# multiplexRGBtry1.net
KiCad netlist of a schematic drawn in EAGLE
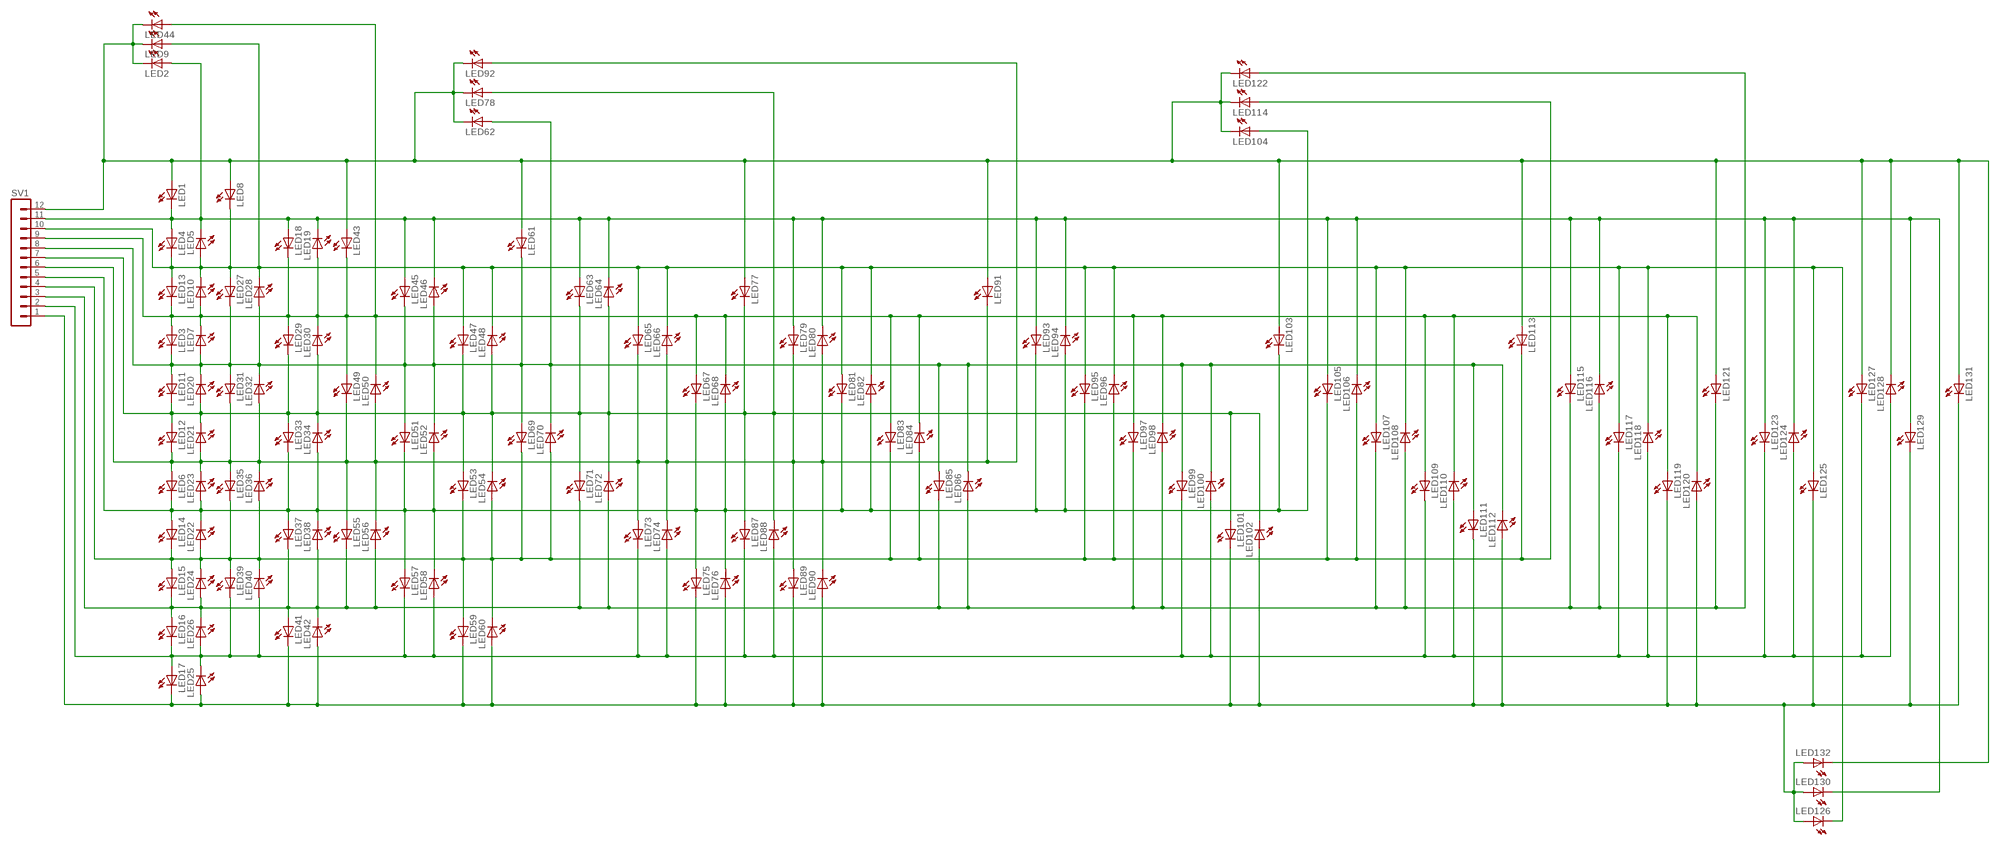
[diagram p0: schematic, sheet 1]

(export (version "E")
  (design (tool "Eeschema 10.0.6"))
  (components
    (comp (ref "LED1")
      (value "LED5MM")
      (footprint "eagle-import:LED5MM")
      (libsource (lib "eagle-import") (part "LED5MM"))
    )
    (comp (ref "LED2")
      (value "LED5MM")
      (footprint "eagle-import:LED5MM")
      (libsource (lib "eagle-import") (part "LED5MM"))
    )
    (comp (ref "LED3")
      (value "LED5MM")
      (footprint "eagle-import:LED5MM")
      (libsource (lib "eagle-import") (part "LED5MM"))
    )
    (comp (ref "LED4")
      (value "LED5MM")
      (footprint "eagle-import:LED5MM")
      (libsource (lib "eagle-import") (part "LED5MM"))
    )
    (comp (ref "LED5")
      (value "LED5MM")
      (footprint "eagle-import:LED5MM")
      (libsource (lib "eagle-import") (part "LED5MM"))
    )
    (comp (ref "LED6")
      (value "LED5MM")
      (footprint "eagle-import:LED5MM")
      (libsource (lib "eagle-import") (part "LED5MM"))
    )
    (comp (ref "LED7")
      (value "LED5MM")
      (footprint "eagle-import:LED5MM")
      (libsource (lib "eagle-import") (part "LED5MM"))
    )
    (comp (ref "LED8")
      (value "LED5MM")
      (footprint "eagle-import:LED5MM")
      (libsource (lib "eagle-import") (part "LED5MM"))
    )
    (comp (ref "LED9")
      (value "LED5MM")
      (footprint "eagle-import:LED5MM")
      (libsource (lib "eagle-import") (part "LED5MM"))
    )
    (comp (ref "LED10")
      (value "LED5MM")
      (footprint "eagle-import:LED5MM")
      (libsource (lib "eagle-import") (part "LED5MM"))
    )
    (comp (ref "LED11")
      (value "LED5MM")
      (footprint "eagle-import:LED5MM")
      (libsource (lib "eagle-import") (part "LED5MM"))
    )
    (comp (ref "LED12")
      (value "LED5MM")
      (footprint "eagle-import:LED5MM")
      (libsource (lib "eagle-import") (part "LED5MM"))
    )
    (comp (ref "LED13")
      (value "LED5MM")
      (footprint "eagle-import:LED5MM")
      (libsource (lib "eagle-import") (part "LED5MM"))
    )
    (comp (ref "LED14")
      (value "LED5MM")
      (footprint "eagle-import:LED5MM")
      (libsource (lib "eagle-import") (part "LED5MM"))
    )
    (comp (ref "LED15")
      (value "LED5MM")
      (footprint "eagle-import:LED5MM")
      (libsource (lib "eagle-import") (part "LED5MM"))
    )
    (comp (ref "LED16")
      (value "LED5MM")
      (footprint "eagle-import:LED5MM")
      (libsource (lib "eagle-import") (part "LED5MM"))
    )
    (comp (ref "LED17")
      (value "LED5MM")
      (footprint "eagle-import:LED5MM")
      (libsource (lib "eagle-import") (part "LED5MM"))
    )
    (comp (ref "LED18")
      (value "LED5MM")
      (footprint "eagle-import:LED5MM")
      (libsource (lib "eagle-import") (part "LED5MM"))
    )
    (comp (ref "LED19")
      (value "LED5MM")
      (footprint "eagle-import:LED5MM")
      (libsource (lib "eagle-import") (part "LED5MM"))
    )
    (comp (ref "LED20")
      (value "LED5MM")
      (footprint "eagle-import:LED5MM")
      (libsource (lib "eagle-import") (part "LED5MM"))
    )
    (comp (ref "LED21")
      (value "LED5MM")
      (footprint "eagle-import:LED5MM")
      (libsource (lib "eagle-import") (part "LED5MM"))
    )
    (comp (ref "LED22")
      (value "LED5MM")
      (footprint "eagle-import:LED5MM")
      (libsource (lib "eagle-import") (part "LED5MM"))
    )
    (comp (ref "LED23")
      (value "LED5MM")
      (footprint "eagle-import:LED5MM")
      (libsource (lib "eagle-import") (part "LED5MM"))
    )
    (comp (ref "LED24")
      (value "LED5MM")
      (footprint "eagle-import:LED5MM")
      (libsource (lib "eagle-import") (part "LED5MM"))
    )
    (comp (ref "LED25")
      (value "LED5MM")
      (footprint "eagle-import:LED5MM")
      (libsource (lib "eagle-import") (part "LED5MM"))
    )
    (comp (ref "LED26")
      (value "LED5MM")
      (footprint "eagle-import:LED5MM")
      (libsource (lib "eagle-import") (part "LED5MM"))
    )
    (comp (ref "LED27")
      (value "LED5MM")
      (footprint "eagle-import:LED5MM")
      (libsource (lib "eagle-import") (part "LED5MM"))
    )
    (comp (ref "LED28")
      (value "LED5MM")
      (footprint "eagle-import:LED5MM")
      (libsource (lib "eagle-import") (part "LED5MM"))
    )
    (comp (ref "LED29")
      (value "LED5MM")
      (footprint "eagle-import:LED5MM")
      (libsource (lib "eagle-import") (part "LED5MM"))
    )
    (comp (ref "LED30")
      (value "LED5MM")
      (footprint "eagle-import:LED5MM")
      (libsource (lib "eagle-import") (part "LED5MM"))
    )
    (comp (ref "LED31")
      (value "LED5MM")
      (footprint "eagle-import:LED5MM")
      (libsource (lib "eagle-import") (part "LED5MM"))
    )
    (comp (ref "LED32")
      (value "LED5MM")
      (footprint "eagle-import:LED5MM")
      (libsource (lib "eagle-import") (part "LED5MM"))
    )
    (comp (ref "LED33")
      (value "LED5MM")
      (footprint "eagle-import:LED5MM")
      (libsource (lib "eagle-import") (part "LED5MM"))
    )
    (comp (ref "LED34")
      (value "LED5MM")
      (footprint "eagle-import:LED5MM")
      (libsource (lib "eagle-import") (part "LED5MM"))
    )
    (comp (ref "LED35")
      (value "LED5MM")
      (footprint "eagle-import:LED5MM")
      (libsource (lib "eagle-import") (part "LED5MM"))
    )
    (comp (ref "LED36")
      (value "LED5MM")
      (footprint "eagle-import:LED5MM")
      (libsource (lib "eagle-import") (part "LED5MM"))
    )
    (comp (ref "LED37")
      (value "LED5MM")
      (footprint "eagle-import:LED5MM")
      (libsource (lib "eagle-import") (part "LED5MM"))
    )
    (comp (ref "LED38")
      (value "LED5MM")
      (footprint "eagle-import:LED5MM")
      (libsource (lib "eagle-import") (part "LED5MM"))
    )
    (comp (ref "LED39")
      (value "LED5MM")
      (footprint "eagle-import:LED5MM")
      (libsource (lib "eagle-import") (part "LED5MM"))
    )
    (comp (ref "LED40")
      (value "LED5MM")
      (footprint "eagle-import:LED5MM")
      (libsource (lib "eagle-import") (part "LED5MM"))
    )
    (comp (ref "LED41")
      (value "LED5MM")
      (footprint "eagle-import:LED5MM")
      (libsource (lib "eagle-import") (part "LED5MM"))
    )
    (comp (ref "LED42")
      (value "LED5MM")
      (footprint "eagle-import:LED5MM")
      (libsource (lib "eagle-import") (part "LED5MM"))
    )
    (comp (ref "LED43")
      (value "LED5MM")
      (footprint "eagle-import:LED5MM")
      (libsource (lib "eagle-import") (part "LED5MM"))
    )
    (comp (ref "LED44")
      (value "LED5MM")
      (footprint "eagle-import:LED5MM")
      (libsource (lib "eagle-import") (part "LED5MM"))
    )
    (comp (ref "LED45")
      (value "LED5MM")
      (footprint "eagle-import:LED5MM")
      (libsource (lib "eagle-import") (part "LED5MM"))
    )
    (comp (ref "LED46")
      (value "LED5MM")
      (footprint "eagle-import:LED5MM")
      (libsource (lib "eagle-import") (part "LED5MM"))
    )
    (comp (ref "LED47")
      (value "LED5MM")
      (footprint "eagle-import:LED5MM")
      (libsource (lib "eagle-import") (part "LED5MM"))
    )
    (comp (ref "LED48")
      (value "LED5MM")
      (footprint "eagle-import:LED5MM")
      (libsource (lib "eagle-import") (part "LED5MM"))
    )
    (comp (ref "LED49")
      (value "LED5MM")
      (footprint "eagle-import:LED5MM")
      (libsource (lib "eagle-import") (part "LED5MM"))
    )
    (comp (ref "LED50")
      (value "LED5MM")
      (footprint "eagle-import:LED5MM")
      (libsource (lib "eagle-import") (part "LED5MM"))
    )
    (comp (ref "LED51")
      (value "LED5MM")
      (footprint "eagle-import:LED5MM")
      (libsource (lib "eagle-import") (part "LED5MM"))
    )
    (comp (ref "LED52")
      (value "LED5MM")
      (footprint "eagle-import:LED5MM")
      (libsource (lib "eagle-import") (part "LED5MM"))
    )
    (comp (ref "LED53")
      (value "LED5MM")
      (footprint "eagle-import:LED5MM")
      (libsource (lib "eagle-import") (part "LED5MM"))
    )
    (comp (ref "LED54")
      (value "LED5MM")
      (footprint "eagle-import:LED5MM")
      (libsource (lib "eagle-import") (part "LED5MM"))
    )
    (comp (ref "LED55")
      (value "LED5MM")
      (footprint "eagle-import:LED5MM")
      (libsource (lib "eagle-import") (part "LED5MM"))
    )
    (comp (ref "LED56")
      (value "LED5MM")
      (footprint "eagle-import:LED5MM")
      (libsource (lib "eagle-import") (part "LED5MM"))
    )
    (comp (ref "LED57")
      (value "LED5MM")
      (footprint "eagle-import:LED5MM")
      (libsource (lib "eagle-import") (part "LED5MM"))
    )
    (comp (ref "LED58")
      (value "LED5MM")
      (footprint "eagle-import:LED5MM")
      (libsource (lib "eagle-import") (part "LED5MM"))
    )
    (comp (ref "LED59")
      (value "LED5MM")
      (footprint "eagle-import:LED5MM")
      (libsource (lib "eagle-import") (part "LED5MM"))
    )
    (comp (ref "LED60")
      (value "LED5MM")
      (footprint "eagle-import:LED5MM")
      (libsource (lib "eagle-import") (part "LED5MM"))
    )
    (comp (ref "LED61")
      (value "LED5MM")
      (footprint "eagle-import:LED5MM")
      (libsource (lib "eagle-import") (part "LED5MM"))
    )
    (comp (ref "LED62")
      (value "LED5MM")
      (footprint "eagle-import:LED5MM")
      (libsource (lib "eagle-import") (part "LED5MM"))
    )
    (comp (ref "LED63")
      (value "LED5MM")
      (footprint "eagle-import:LED5MM")
      (libsource (lib "eagle-import") (part "LED5MM"))
    )
    (comp (ref "LED64")
      (value "LED5MM")
      (footprint "eagle-import:LED5MM")
      (libsource (lib "eagle-import") (part "LED5MM"))
    )
    (comp (ref "LED65")
      (value "LED5MM")
      (footprint "eagle-import:LED5MM")
      (libsource (lib "eagle-import") (part "LED5MM"))
    )
    (comp (ref "LED66")
      (value "LED5MM")
      (footprint "eagle-import:LED5MM")
      (libsource (lib "eagle-import") (part "LED5MM"))
    )
    (comp (ref "LED67")
      (value "LED5MM")
      (footprint "eagle-import:LED5MM")
      (libsource (lib "eagle-import") (part "LED5MM"))
    )
    (comp (ref "LED68")
      (value "LED5MM")
      (footprint "eagle-import:LED5MM")
      (libsource (lib "eagle-import") (part "LED5MM"))
    )
    (comp (ref "LED69")
      (value "LED5MM")
      (footprint "eagle-import:LED5MM")
      (libsource (lib "eagle-import") (part "LED5MM"))
    )
    (comp (ref "LED70")
      (value "LED5MM")
      (footprint "eagle-import:LED5MM")
      (libsource (lib "eagle-import") (part "LED5MM"))
    )
    (comp (ref "LED71")
      (value "LED5MM")
      (footprint "eagle-import:LED5MM")
      (libsource (lib "eagle-import") (part "LED5MM"))
    )
    (comp (ref "LED72")
      (value "LED5MM")
      (footprint "eagle-import:LED5MM")
      (libsource (lib "eagle-import") (part "LED5MM"))
    )
    (comp (ref "LED73")
      (value "LED5MM")
      (footprint "eagle-import:LED5MM")
      (libsource (lib "eagle-import") (part "LED5MM"))
    )
    (comp (ref "LED74")
      (value "LED5MM")
      (footprint "eagle-import:LED5MM")
      (libsource (lib "eagle-import") (part "LED5MM"))
    )
    (comp (ref "LED75")
      (value "LED5MM")
      (footprint "eagle-import:LED5MM")
      (libsource (lib "eagle-import") (part "LED5MM"))
    )
    (comp (ref "LED76")
      (value "LED5MM")
      (footprint "eagle-import:LED5MM")
      (libsource (lib "eagle-import") (part "LED5MM"))
    )
    (comp (ref "LED77")
      (value "LED5MM")
      (footprint "eagle-import:LED5MM")
      (libsource (lib "eagle-import") (part "LED5MM"))
    )
    (comp (ref "LED78")
      (value "LED5MM")
      (footprint "eagle-import:LED5MM")
      (libsource (lib "eagle-import") (part "LED5MM"))
    )
    (comp (ref "LED79")
      (value "LED5MM")
      (footprint "eagle-import:LED5MM")
      (libsource (lib "eagle-import") (part "LED5MM"))
    )
    (comp (ref "LED80")
      (value "LED5MM")
      (footprint "eagle-import:LED5MM")
      (libsource (lib "eagle-import") (part "LED5MM"))
    )
    (comp (ref "LED81")
      (value "LED5MM")
      (footprint "eagle-import:LED5MM")
      (libsource (lib "eagle-import") (part "LED5MM"))
    )
    (comp (ref "LED82")
      (value "LED5MM")
      (footprint "eagle-import:LED5MM")
      (libsource (lib "eagle-import") (part "LED5MM"))
    )
    (comp (ref "LED83")
      (value "LED5MM")
      (footprint "eagle-import:LED5MM")
      (libsource (lib "eagle-import") (part "LED5MM"))
    )
    (comp (ref "LED84")
      (value "LED5MM")
      (footprint "eagle-import:LED5MM")
      (libsource (lib "eagle-import") (part "LED5MM"))
    )
    (comp (ref "LED85")
      (value "LED5MM")
      (footprint "eagle-import:LED5MM")
      (libsource (lib "eagle-import") (part "LED5MM"))
    )
    (comp (ref "LED86")
      (value "LED5MM")
      (footprint "eagle-import:LED5MM")
      (libsource (lib "eagle-import") (part "LED5MM"))
    )
    (comp (ref "LED87")
      (value "LED5MM")
      (footprint "eagle-import:LED5MM")
      (libsource (lib "eagle-import") (part "LED5MM"))
    )
    (comp (ref "LED88")
      (value "LED5MM")
      (footprint "eagle-import:LED5MM")
      (libsource (lib "eagle-import") (part "LED5MM"))
    )
    (comp (ref "LED89")
      (value "LED5MM")
      (footprint "eagle-import:LED5MM")
      (libsource (lib "eagle-import") (part "LED5MM"))
    )
    (comp (ref "LED90")
      (value "LED5MM")
      (footprint "eagle-import:LED5MM")
      (libsource (lib "eagle-import") (part "LED5MM"))
    )
    (comp (ref "LED91")
      (value "LED5MM")
      (footprint "eagle-import:LED5MM")
      (libsource (lib "eagle-import") (part "LED5MM"))
    )
    (comp (ref "LED92")
      (value "LED5MM")
      (footprint "eagle-import:LED5MM")
      (libsource (lib "eagle-import") (part "LED5MM"))
    )
    (comp (ref "LED93")
      (value "LED5MM")
      (footprint "eagle-import:LED5MM")
      (libsource (lib "eagle-import") (part "LED5MM"))
    )
    (comp (ref "LED94")
      (value "LED5MM")
      (footprint "eagle-import:LED5MM")
      (libsource (lib "eagle-import") (part "LED5MM"))
    )
    (comp (ref "LED95")
      (value "LED5MM")
      (footprint "eagle-import:LED5MM")
      (libsource (lib "eagle-import") (part "LED5MM"))
    )
    (comp (ref "LED96")
      (value "LED5MM")
      (footprint "eagle-import:LED5MM")
      (libsource (lib "eagle-import") (part "LED5MM"))
    )
    (comp (ref "LED97")
      (value "LED5MM")
      (footprint "eagle-import:LED5MM")
      (libsource (lib "eagle-import") (part "LED5MM"))
    )
    (comp (ref "LED98")
      (value "LED5MM")
      (footprint "eagle-import:LED5MM")
      (libsource (lib "eagle-import") (part "LED5MM"))
    )
    (comp (ref "LED99")
      (value "LED5MM")
      (footprint "eagle-import:LED5MM")
      (libsource (lib "eagle-import") (part "LED5MM"))
    )
    (comp (ref "LED100")
      (value "LED5MM")
      (footprint "eagle-import:LED5MM")
      (libsource (lib "eagle-import") (part "LED5MM"))
    )
    (comp (ref "LED101")
      (value "LED5MM")
      (footprint "eagle-import:LED5MM")
      (libsource (lib "eagle-import") (part "LED5MM"))
    )
    (comp (ref "LED102")
      (value "LED5MM")
      (footprint "eagle-import:LED5MM")
      (libsource (lib "eagle-import") (part "LED5MM"))
    )
    (comp (ref "LED103")
      (value "LED5MM")
      (footprint "eagle-import:LED5MM")
      (libsource (lib "eagle-import") (part "LED5MM"))
    )
    (comp (ref "LED104")
      (value "LED5MM")
      (footprint "eagle-import:LED5MM")
      (libsource (lib "eagle-import") (part "LED5MM"))
    )
    (comp (ref "LED105")
      (value "LED5MM")
      (footprint "eagle-import:LED5MM")
      (libsource (lib "eagle-import") (part "LED5MM"))
    )
    (comp (ref "LED106")
      (value "LED5MM")
      (footprint "eagle-import:LED5MM")
      (libsource (lib "eagle-import") (part "LED5MM"))
    )
    (comp (ref "LED107")
      (value "LED5MM")
      (footprint "eagle-import:LED5MM")
      (libsource (lib "eagle-import") (part "LED5MM"))
    )
    (comp (ref "LED108")
      (value "LED5MM")
      (footprint "eagle-import:LED5MM")
      (libsource (lib "eagle-import") (part "LED5MM"))
    )
    (comp (ref "LED109")
      (value "LED5MM")
      (footprint "eagle-import:LED5MM")
      (libsource (lib "eagle-import") (part "LED5MM"))
    )
    (comp (ref "LED110")
      (value "LED5MM")
      (footprint "eagle-import:LED5MM")
      (libsource (lib "eagle-import") (part "LED5MM"))
    )
    (comp (ref "LED111")
      (value "LED5MM")
      (footprint "eagle-import:LED5MM")
      (libsource (lib "eagle-import") (part "LED5MM"))
    )
    (comp (ref "LED112")
      (value "LED5MM")
      (footprint "eagle-import:LED5MM")
      (libsource (lib "eagle-import") (part "LED5MM"))
    )
    (comp (ref "LED113")
      (value "LED5MM")
      (footprint "eagle-import:LED5MM")
      (libsource (lib "eagle-import") (part "LED5MM"))
    )
    (comp (ref "LED114")
      (value "LED5MM")
      (footprint "eagle-import:LED5MM")
      (libsource (lib "eagle-import") (part "LED5MM"))
    )
    (comp (ref "LED115")
      (value "LED5MM")
      (footprint "eagle-import:LED5MM")
      (libsource (lib "eagle-import") (part "LED5MM"))
    )
    (comp (ref "LED116")
      (value "LED5MM")
      (footprint "eagle-import:LED5MM")
      (libsource (lib "eagle-import") (part "LED5MM"))
    )
    (comp (ref "LED117")
      (value "LED5MM")
      (footprint "eagle-import:LED5MM")
      (libsource (lib "eagle-import") (part "LED5MM"))
    )
    (comp (ref "LED118")
      (value "LED5MM")
      (footprint "eagle-import:LED5MM")
      (libsource (lib "eagle-import") (part "LED5MM"))
    )
    (comp (ref "LED119")
      (value "LED5MM")
      (footprint "eagle-import:LED5MM")
      (libsource (lib "eagle-import") (part "LED5MM"))
    )
    (comp (ref "LED120")
      (value "LED5MM")
      (footprint "eagle-import:LED5MM")
      (libsource (lib "eagle-import") (part "LED5MM"))
    )
    (comp (ref "LED121")
      (value "LED5MM")
      (footprint "eagle-import:LED5MM")
      (libsource (lib "eagle-import") (part "LED5MM"))
    )
    (comp (ref "LED122")
      (value "LED5MM")
      (footprint "eagle-import:LED5MM")
      (libsource (lib "eagle-import") (part "LED5MM"))
    )
    (comp (ref "LED123")
      (value "LED5MM")
      (footprint "eagle-import:LED5MM")
      (libsource (lib "eagle-import") (part "LED5MM"))
    )
    (comp (ref "LED124")
      (value "LED5MM")
      (footprint "eagle-import:LED5MM")
      (libsource (lib "eagle-import") (part "LED5MM"))
    )
    (comp (ref "LED125")
      (value "LED5MM")
      (footprint "eagle-import:LED5MM")
      (libsource (lib "eagle-import") (part "LED5MM"))
    )
    (comp (ref "LED126")
      (value "LED5MM")
      (footprint "eagle-import:LED5MM")
      (libsource (lib "eagle-import") (part "LED5MM"))
    )
    (comp (ref "LED127")
      (value "LED5MM")
      (footprint "eagle-import:LED5MM")
      (libsource (lib "eagle-import") (part "LED5MM"))
    )
    (comp (ref "LED128")
      (value "LED5MM")
      (footprint "eagle-import:LED5MM")
      (libsource (lib "eagle-import") (part "LED5MM"))
    )
    (comp (ref "LED129")
      (value "LED5MM")
      (footprint "eagle-import:LED5MM")
      (libsource (lib "eagle-import") (part "LED5MM"))
    )
    (comp (ref "LED130")
      (value "LED5MM")
      (footprint "eagle-import:LED5MM")
      (libsource (lib "eagle-import") (part "LED5MM"))
    )
    (comp (ref "LED131")
      (value "LED5MM")
      (footprint "eagle-import:LED5MM")
      (libsource (lib "eagle-import") (part "LED5MM"))
    )
    (comp (ref "LED132")
      (value "LED5MM")
      (footprint "eagle-import:LED5MM")
      (libsource (lib "eagle-import") (part "LED5MM"))
    )
    (comp (ref "SV1")
      (value "MA12-1")
      (footprint "eagle-import:MA12-1")
      (libsource (lib "eagle-import") (part "MA12-1"))
    )
  )
  (nets
    (net (code "1") (name "Net-(LED1-C)") (class "Default")
      (node (ref "LED1") (pin "K") (pinfunction "C_K") (pintype "passive"))
      (node (ref "LED105") (pin "A") (pinfunction "A_A") (pintype "passive"))
      (node (ref "LED106") (pin "K") (pinfunction "C_K") (pintype "passive"))
      (node (ref "LED115") (pin "A") (pinfunction "A_A") (pintype "passive"))
      (node (ref "LED116") (pin "K") (pinfunction "C_K") (pintype "passive"))
      (node (ref "LED123") (pin "A") (pinfunction "A_A") (pintype "passive"))
      (node (ref "LED124") (pin "K") (pinfunction "C_K") (pintype "passive"))
      (node (ref "LED129") (pin "A") (pinfunction "A_A") (pintype "passive"))
      (node (ref "LED130") (pin "K") (pinfunction "C_K") (pintype "passive"))
      (node (ref "LED18") (pin "A") (pinfunction "A_A") (pintype "passive"))
      (node (ref "LED19") (pin "K") (pinfunction "C_K") (pintype "passive"))
      (node (ref "LED2") (pin "A") (pinfunction "A_A") (pintype "passive"))
      (node (ref "LED4") (pin "A") (pinfunction "A_A") (pintype "passive"))
      (node (ref "LED45") (pin "A") (pinfunction "A_A") (pintype "passive"))
      (node (ref "LED46") (pin "K") (pinfunction "C_K") (pintype "passive"))
      (node (ref "LED5") (pin "K") (pinfunction "C_K") (pintype "passive"))
      (node (ref "LED63") (pin "A") (pinfunction "A_A") (pintype "passive"))
      (node (ref "LED64") (pin "K") (pinfunction "C_K") (pintype "passive"))
      (node (ref "LED79") (pin "A") (pinfunction "A_A") (pintype "passive"))
      (node (ref "LED80") (pin "K") (pinfunction "C_K") (pintype "passive"))
      (node (ref "LED93") (pin "A") (pinfunction "A_A") (pintype "passive"))
      (node (ref "LED94") (pin "K") (pinfunction "C_K") (pintype "passive"))
      (node (ref "SV1") (pin "11") (pinfunction "11_11") (pintype "passive"))
    )
    (net (code "2") (name "Net-(LED10-C)") (class "Default")
      (node (ref "LED10") (pin "K") (pinfunction "C_K") (pintype "passive"))
      (node (ref "LED107") (pin "A") (pinfunction "A_A") (pintype "passive"))
      (node (ref "LED108") (pin "K") (pinfunction "C_K") (pintype "passive"))
      (node (ref "LED117") (pin "A") (pinfunction "A_A") (pintype "passive"))
      (node (ref "LED118") (pin "K") (pinfunction "C_K") (pintype "passive"))
      (node (ref "LED125") (pin "A") (pinfunction "A_A") (pintype "passive"))
      (node (ref "LED126") (pin "K") (pinfunction "C_K") (pintype "passive"))
      (node (ref "LED13") (pin "A") (pinfunction "A_A") (pintype "passive"))
      (node (ref "LED27") (pin "A") (pinfunction "A_A") (pintype "passive"))
      (node (ref "LED28") (pin "K") (pinfunction "C_K") (pintype "passive"))
      (node (ref "LED4") (pin "K") (pinfunction "C_K") (pintype "passive"))
      (node (ref "LED47") (pin "A") (pinfunction "A_A") (pintype "passive"))
      (node (ref "LED48") (pin "K") (pinfunction "C_K") (pintype "passive"))
      (node (ref "LED5") (pin "A") (pinfunction "A_A") (pintype "passive"))
      (node (ref "LED65") (pin "A") (pinfunction "A_A") (pintype "passive"))
      (node (ref "LED66") (pin "K") (pinfunction "C_K") (pintype "passive"))
      (node (ref "LED8") (pin "K") (pinfunction "C_K") (pintype "passive"))
      (node (ref "LED81") (pin "A") (pinfunction "A_A") (pintype "passive"))
      (node (ref "LED82") (pin "K") (pinfunction "C_K") (pintype "passive"))
      (node (ref "LED9") (pin "A") (pinfunction "A_A") (pintype "passive"))
      (node (ref "LED95") (pin "A") (pinfunction "A_A") (pintype "passive"))
      (node (ref "LED96") (pin "K") (pinfunction "C_K") (pintype "passive"))
      (node (ref "SV1") (pin "10") (pinfunction "10_10") (pintype "passive"))
    )
    (net (code "3") (name "Net-(LED12-C)") (class "Default")
      (node (ref "LED12") (pin "K") (pinfunction "C_K") (pintype "passive"))
      (node (ref "LED21") (pin "A") (pinfunction "A_A") (pintype "passive"))
      (node (ref "LED23") (pin "K") (pinfunction "C_K") (pintype "passive"))
      (node (ref "LED31") (pin "K") (pinfunction "C_K") (pintype "passive"))
      (node (ref "LED32") (pin "A") (pinfunction "A_A") (pintype "passive"))
      (node (ref "LED35") (pin "A") (pinfunction "A_A") (pintype "passive"))
      (node (ref "LED36") (pin "K") (pinfunction "C_K") (pintype "passive"))
      (node (ref "LED49") (pin "K") (pinfunction "C_K") (pintype "passive"))
      (node (ref "LED50") (pin "A") (pinfunction "A_A") (pintype "passive"))
      (node (ref "LED55") (pin "A") (pinfunction "A_A") (pintype "passive"))
      (node (ref "LED56") (pin "K") (pinfunction "C_K") (pintype "passive"))
      (node (ref "LED6") (pin "A") (pinfunction "A_A") (pintype "passive"))
      (node (ref "LED65") (pin "K") (pinfunction "C_K") (pintype "passive"))
      (node (ref "LED66") (pin "A") (pinfunction "A_A") (pintype "passive"))
      (node (ref "LED73") (pin "A") (pinfunction "A_A") (pintype "passive"))
      (node (ref "LED74") (pin "K") (pinfunction "C_K") (pintype "passive"))
      (node (ref "LED79") (pin "K") (pinfunction "C_K") (pintype "passive"))
      (node (ref "LED80") (pin "A") (pinfunction "A_A") (pintype "passive"))
      (node (ref "LED89") (pin "A") (pinfunction "A_A") (pintype "passive"))
      (node (ref "LED90") (pin "K") (pinfunction "C_K") (pintype "passive"))
      (node (ref "LED91") (pin "K") (pinfunction "C_K") (pintype "passive"))
      (node (ref "LED92") (pin "A") (pinfunction "A_A") (pintype "passive"))
      (node (ref "SV1") (pin "6") (pinfunction "6_6") (pintype "passive"))
    )
    (net (code "4") (name "Net-(LED100-C)") (class "Default")
      (node (ref "LED100") (pin "K") (pinfunction "C_K") (pintype "passive"))
      (node (ref "LED11") (pin "A") (pinfunction "A_A") (pintype "passive"))
      (node (ref "LED111") (pin "A") (pinfunction "A_A") (pintype "passive"))
      (node (ref "LED112") (pin "K") (pinfunction "C_K") (pintype "passive"))
      (node (ref "LED20") (pin "K") (pinfunction "C_K") (pintype "passive"))
      (node (ref "LED27") (pin "K") (pinfunction "C_K") (pintype "passive"))
      (node (ref "LED28") (pin "A") (pinfunction "A_A") (pintype "passive"))
      (node (ref "LED3") (pin "K") (pinfunction "C_K") (pintype "passive"))
      (node (ref "LED31") (pin "A") (pinfunction "A_A") (pintype "passive"))
      (node (ref "LED32") (pin "K") (pinfunction "C_K") (pintype "passive"))
      (node (ref "LED45") (pin "K") (pinfunction "C_K") (pintype "passive"))
      (node (ref "LED46") (pin "A") (pinfunction "A_A") (pintype "passive"))
      (node (ref "LED51") (pin "A") (pinfunction "A_A") (pintype "passive"))
      (node (ref "LED52") (pin "K") (pinfunction "C_K") (pintype "passive"))
      (node (ref "LED61") (pin "K") (pinfunction "C_K") (pintype "passive"))
      (node (ref "LED62") (pin "A") (pinfunction "A_A") (pintype "passive"))
      (node (ref "LED69") (pin "A") (pinfunction "A_A") (pintype "passive"))
      (node (ref "LED7") (pin "A") (pinfunction "A_A") (pintype "passive"))
      (node (ref "LED70") (pin "K") (pinfunction "C_K") (pintype "passive"))
      (node (ref "LED85") (pin "A") (pinfunction "A_A") (pintype "passive"))
      (node (ref "LED86") (pin "K") (pinfunction "C_K") (pintype "passive"))
      (node (ref "LED99") (pin "A") (pinfunction "A_A") (pintype "passive"))
      (node (ref "SV1") (pin "8") (pinfunction "8_8") (pintype "passive"))
    )
    (net (code "5") (name "Net-(LED101-C)") (class "Default")
      (node (ref "LED101") (pin "K") (pinfunction "C_K") (pintype "passive"))
      (node (ref "LED102") (pin "A") (pinfunction "A_A") (pintype "passive"))
      (node (ref "LED111") (pin "K") (pinfunction "C_K") (pintype "passive"))
      (node (ref "LED112") (pin "A") (pinfunction "A_A") (pintype "passive"))
      (node (ref "LED119") (pin "K") (pinfunction "C_K") (pintype "passive"))
      (node (ref "LED120") (pin "A") (pinfunction "A_A") (pintype "passive"))
      (node (ref "LED125") (pin "K") (pinfunction "C_K") (pintype "passive"))
      (node (ref "LED126") (pin "A") (pinfunction "A_A") (pintype "passive"))
      (node (ref "LED129") (pin "K") (pinfunction "C_K") (pintype "passive"))
      (node (ref "LED130") (pin "A") (pinfunction "A_A") (pintype "passive"))
      (node (ref "LED131") (pin "K") (pinfunction "C_K") (pintype "passive"))
      (node (ref "LED132") (pin "A") (pinfunction "A_A") (pintype "passive"))
      (node (ref "LED17") (pin "K") (pinfunction "C_K") (pintype "passive"))
      (node (ref "LED25") (pin "A") (pinfunction "A_A") (pintype "passive"))
      (node (ref "LED41") (pin "K") (pinfunction "C_K") (pintype "passive"))
      (node (ref "LED42") (pin "A") (pinfunction "A_A") (pintype "passive"))
      (node (ref "LED59") (pin "K") (pinfunction "C_K") (pintype "passive"))
      (node (ref "LED60") (pin "A") (pinfunction "A_A") (pintype "passive"))
      (node (ref "LED75") (pin "K") (pinfunction "C_K") (pintype "passive"))
      (node (ref "LED76") (pin "A") (pinfunction "A_A") (pintype "passive"))
      (node (ref "LED89") (pin "K") (pinfunction "C_K") (pintype "passive"))
      (node (ref "LED90") (pin "A") (pinfunction "A_A") (pintype "passive"))
      (node (ref "SV1") (pin "1") (pinfunction "1_1") (pintype "passive"))
    )
    (net (code "6") (name "Net-(LED102-C)") (class "Default")
      (node (ref "LED101") (pin "A") (pinfunction "A_A") (pintype "passive"))
      (node (ref "LED102") (pin "K") (pinfunction "C_K") (pintype "passive"))
      (node (ref "LED11") (pin "K") (pinfunction "C_K") (pintype "passive"))
      (node (ref "LED12") (pin "A") (pinfunction "A_A") (pintype "passive"))
      (node (ref "LED20") (pin "A") (pinfunction "A_A") (pintype "passive"))
      (node (ref "LED21") (pin "K") (pinfunction "C_K") (pintype "passive"))
      (node (ref "LED29") (pin "K") (pinfunction "C_K") (pintype "passive"))
      (node (ref "LED30") (pin "A") (pinfunction "A_A") (pintype "passive"))
      (node (ref "LED33") (pin "A") (pinfunction "A_A") (pintype "passive"))
      (node (ref "LED34") (pin "K") (pinfunction "C_K") (pintype "passive"))
      (node (ref "LED47") (pin "K") (pinfunction "C_K") (pintype "passive"))
      (node (ref "LED48") (pin "A") (pinfunction "A_A") (pintype "passive"))
      (node (ref "LED53") (pin "A") (pinfunction "A_A") (pintype "passive"))
      (node (ref "LED54") (pin "K") (pinfunction "C_K") (pintype "passive"))
      (node (ref "LED63") (pin "K") (pinfunction "C_K") (pintype "passive"))
      (node (ref "LED64") (pin "A") (pinfunction "A_A") (pintype "passive"))
      (node (ref "LED71") (pin "A") (pinfunction "A_A") (pintype "passive"))
      (node (ref "LED72") (pin "K") (pinfunction "C_K") (pintype "passive"))
      (node (ref "LED77") (pin "K") (pinfunction "C_K") (pintype "passive"))
      (node (ref "LED78") (pin "A") (pinfunction "A_A") (pintype "passive"))
      (node (ref "LED87") (pin "A") (pinfunction "A_A") (pintype "passive"))
      (node (ref "LED88") (pin "K") (pinfunction "C_K") (pintype "passive"))
      (node (ref "SV1") (pin "7") (pinfunction "7_7") (pintype "passive"))
    )
    (net (code "7") (name "Net-(LED103-C)") (class "Default")
      (node (ref "LED103") (pin "K") (pinfunction "C_K") (pintype "passive"))
      (node (ref "LED104") (pin "A") (pinfunction "A_A") (pintype "passive"))
      (node (ref "LED14") (pin "A") (pinfunction "A_A") (pintype "passive"))
      (node (ref "LED22") (pin "K") (pinfunction "C_K") (pintype "passive"))
      (node (ref "LED23") (pin "A") (pinfunction "A_A") (pintype "passive"))
      (node (ref "LED33") (pin "K") (pinfunction "C_K") (pintype "passive"))
      (node (ref "LED34") (pin "A") (pinfunction "A_A") (pintype "passive"))
      (node (ref "LED37") (pin "A") (pinfunction "A_A") (pintype "passive"))
      (node (ref "LED38") (pin "K") (pinfunction "C_K") (pintype "passive"))
      (node (ref "LED51") (pin "K") (pinfunction "C_K") (pintype "passive"))
      (node (ref "LED52") (pin "A") (pinfunction "A_A") (pintype "passive"))
      (node (ref "LED57") (pin "A") (pinfunction "A_A") (pintype "passive"))
      (node (ref "LED58") (pin "K") (pinfunction "C_K") (pintype "passive"))
      (node (ref "LED6") (pin "K") (pinfunction "C_K") (pintype "passive"))
      (node (ref "LED67") (pin "K") (pinfunction "C_K") (pintype "passive"))
      (node (ref "LED68") (pin "A") (pinfunction "A_A") (pintype "passive"))
      (node (ref "LED75") (pin "A") (pinfunction "A_A") (pintype "passive"))
      (node (ref "LED76") (pin "K") (pinfunction "C_K") (pintype "passive"))
      (node (ref "LED81") (pin "K") (pinfunction "C_K") (pintype "passive"))
      (node (ref "LED82") (pin "A") (pinfunction "A_A") (pintype "passive"))
      (node (ref "LED93") (pin "K") (pinfunction "C_K") (pintype "passive"))
      (node (ref "LED94") (pin "A") (pinfunction "A_A") (pintype "passive"))
      (node (ref "SV1") (pin "5") (pinfunction "5_5") (pintype "passive"))
    )
    (net (code "8") (name "Net-(LED104-C)") (class "Default")
      (node (ref "LED1") (pin "A") (pinfunction "A_A") (pintype "passive"))
      (node (ref "LED103") (pin "A") (pinfunction "A_A") (pintype "passive"))
      (node (ref "LED104") (pin "K") (pinfunction "C_K") (pintype "passive"))
      (node (ref "LED113") (pin "A") (pinfunction "A_A") (pintype "passive"))
      (node (ref "LED114") (pin "K") (pinfunction "C_K") (pintype "passive"))
      (node (ref "LED121") (pin "A") (pinfunction "A_A") (pintype "passive"))
      (node (ref "LED122") (pin "K") (pinfunction "C_K") (pintype "passive"))
      (node (ref "LED127") (pin "A") (pinfunction "A_A") (pintype "passive"))
      (node (ref "LED128") (pin "K") (pinfunction "C_K") (pintype "passive"))
      (node (ref "LED131") (pin "A") (pinfunction "A_A") (pintype "passive"))
      (node (ref "LED132") (pin "K") (pinfunction "C_K") (pintype "passive"))
      (node (ref "LED2") (pin "K") (pinfunction "C_K") (pintype "passive"))
      (node (ref "LED43") (pin "A") (pinfunction "A_A") (pintype "passive"))
      (node (ref "LED44") (pin "K") (pinfunction "C_K") (pintype "passive"))
      (node (ref "LED61") (pin "A") (pinfunction "A_A") (pintype "passive"))
      (node (ref "LED62") (pin "K") (pinfunction "C_K") (pintype "passive"))
      (node (ref "LED77") (pin "A") (pinfunction "A_A") (pintype "passive"))
      (node (ref "LED78") (pin "K") (pinfunction "C_K") (pintype "passive"))
      (node (ref "LED8") (pin "A") (pinfunction "A_A") (pintype "passive"))
      (node (ref "LED9") (pin "K") (pinfunction "C_K") (pintype "passive"))
      (node (ref "LED91") (pin "A") (pinfunction "A_A") (pintype "passive"))
      (node (ref "LED92") (pin "K") (pinfunction "C_K") (pintype "passive"))
      (node (ref "SV1") (pin "12") (pinfunction "12_12") (pintype "passive"))
    )
    (net (code "9") (name "Net-(LED105-C)") (class "Default")
      (node (ref "LED105") (pin "K") (pinfunction "C_K") (pintype "passive"))
      (node (ref "LED106") (pin "A") (pinfunction "A_A") (pintype "passive"))
      (node (ref "LED113") (pin "K") (pinfunction "C_K") (pintype "passive"))
      (node (ref "LED114") (pin "A") (pinfunction "A_A") (pintype "passive"))
      (node (ref "LED14") (pin "K") (pinfunction "C_K") (pintype "passive"))
      (node (ref "LED15") (pin "A") (pinfunction "A_A") (pintype "passive"))
      (node (ref "LED22") (pin "A") (pinfunction "A_A") (pintype "passive"))
      (node (ref "LED24") (pin "K") (pinfunction "C_K") (pintype "passive"))
      (node (ref "LED35") (pin "K") (pinfunction "C_K") (pintype "passive"))
      (node (ref "LED36") (pin "A") (pinfunction "A_A") (pintype "passive"))
      (node (ref "LED39") (pin "A") (pinfunction "A_A") (pintype "passive"))
      (node (ref "LED40") (pin "K") (pinfunction "C_K") (pintype "passive"))
      (node (ref "LED53") (pin "K") (pinfunction "C_K") (pintype "passive"))
      (node (ref "LED54") (pin "A") (pinfunction "A_A") (pintype "passive"))
      (node (ref "LED59") (pin "A") (pinfunction "A_A") (pintype "passive"))
      (node (ref "LED60") (pin "K") (pinfunction "C_K") (pintype "passive"))
      (node (ref "LED69") (pin "K") (pinfunction "C_K") (pintype "passive"))
      (node (ref "LED70") (pin "A") (pinfunction "A_A") (pintype "passive"))
      (node (ref "LED83") (pin "K") (pinfunction "C_K") (pintype "passive"))
      (node (ref "LED84") (pin "A") (pinfunction "A_A") (pintype "passive"))
      (node (ref "LED95") (pin "K") (pinfunction "C_K") (pintype "passive"))
      (node (ref "LED96") (pin "A") (pinfunction "A_A") (pintype "passive"))
      (node (ref "SV1") (pin "4") (pinfunction "4_4") (pintype "passive"))
    )
    (net (code "10") (name "Net-(LED107-C)") (class "Default")
      (node (ref "LED107") (pin "K") (pinfunction "C_K") (pintype "passive"))
      (node (ref "LED108") (pin "A") (pinfunction "A_A") (pintype "passive"))
      (node (ref "LED115") (pin "K") (pinfunction "C_K") (pintype "passive"))
      (node (ref "LED116") (pin "A") (pinfunction "A_A") (pintype "passive"))
      (node (ref "LED121") (pin "K") (pinfunction "C_K") (pintype "passive"))
      (node (ref "LED122") (pin "A") (pinfunction "A_A") (pintype "passive"))
      (node (ref "LED15") (pin "K") (pinfunction "C_K") (pintype "passive"))
      (node (ref "LED16") (pin "A") (pinfunction "A_A") (pintype "passive"))
      (node (ref "LED24") (pin "A") (pinfunction "A_A") (pintype "passive"))
      (node (ref "LED26") (pin "K") (pinfunction "C_K") (pintype "passive"))
      (node (ref "LED37") (pin "K") (pinfunction "C_K") (pintype "passive"))
      (node (ref "LED38") (pin "A") (pinfunction "A_A") (pintype "passive"))
      (node (ref "LED41") (pin "A") (pinfunction "A_A") (pintype "passive"))
      (node (ref "LED42") (pin "K") (pinfunction "C_K") (pintype "passive"))
      (node (ref "LED55") (pin "K") (pinfunction "C_K") (pintype "passive"))
      (node (ref "LED56") (pin "A") (pinfunction "A_A") (pintype "passive"))
      (node (ref "LED71") (pin "K") (pinfunction "C_K") (pintype "passive"))
      (node (ref "LED72") (pin "A") (pinfunction "A_A") (pintype "passive"))
      (node (ref "LED85") (pin "K") (pinfunction "C_K") (pintype "passive"))
      (node (ref "LED86") (pin "A") (pinfunction "A_A") (pintype "passive"))
      (node (ref "LED97") (pin "K") (pinfunction "C_K") (pintype "passive"))
      (node (ref "LED98") (pin "A") (pinfunction "A_A") (pintype "passive"))
      (node (ref "SV1") (pin "3") (pinfunction "3_3") (pintype "passive"))
    )
    (net (code "11") (name "Net-(LED109-C)") (class "Default")
      (node (ref "LED100") (pin "A") (pinfunction "A_A") (pintype "passive"))
      (node (ref "LED109") (pin "K") (pinfunction "C_K") (pintype "passive"))
      (node (ref "LED110") (pin "A") (pinfunction "A_A") (pintype "passive"))
      (node (ref "LED117") (pin "K") (pinfunction "C_K") (pintype "passive"))
      (node (ref "LED118") (pin "A") (pinfunction "A_A") (pintype "passive"))
      (node (ref "LED123") (pin "K") (pinfunction "C_K") (pintype "passive"))
      (node (ref "LED124") (pin "A") (pinfunction "A_A") (pintype "passive"))
      (node (ref "LED127") (pin "K") (pinfunction "C_K") (pintype "passive"))
      (node (ref "LED128") (pin "A") (pinfunction "A_A") (pintype "passive"))
      (node (ref "LED16") (pin "K") (pinfunction "C_K") (pintype "passive"))
      (node (ref "LED17") (pin "A") (pinfunction "A_A") (pintype "passive"))
      (node (ref "LED25") (pin "K") (pinfunction "C_K") (pintype "passive"))
      (node (ref "LED26") (pin "A") (pinfunction "A_A") (pintype "passive"))
      (node (ref "LED39") (pin "K") (pinfunction "C_K") (pintype "passive"))
      (node (ref "LED40") (pin "A") (pinfunction "A_A") (pintype "passive"))
      (node (ref "LED57") (pin "K") (pinfunction "C_K") (pintype "passive"))
      (node (ref "LED58") (pin "A") (pinfunction "A_A") (pintype "passive"))
      (node (ref "LED73") (pin "K") (pinfunction "C_K") (pintype "passive"))
      (node (ref "LED74") (pin "A") (pinfunction "A_A") (pintype "passive"))
      (node (ref "LED87") (pin "K") (pinfunction "C_K") (pintype "passive"))
      (node (ref "LED88") (pin "A") (pinfunction "A_A") (pintype "passive"))
      (node (ref "LED99") (pin "K") (pinfunction "C_K") (pintype "passive"))
      (node (ref "SV1") (pin "2") (pinfunction "2_2") (pintype "passive"))
    )
    (net (code "12") (name "Net-(LED110-C)") (class "Default")
      (node (ref "LED10") (pin "A") (pinfunction "A_A") (pintype "passive"))
      (node (ref "LED109") (pin "A") (pinfunction "A_A") (pintype "passive"))
      (node (ref "LED110") (pin "K") (pinfunction "C_K") (pintype "passive"))
      (node (ref "LED119") (pin "A") (pinfunction "A_A") (pintype "passive"))
      (node (ref "LED120") (pin "K") (pinfunction "C_K") (pintype "passive"))
      (node (ref "LED13") (pin "K") (pinfunction "C_K") (pintype "passive"))
      (node (ref "LED18") (pin "K") (pinfunction "C_K") (pintype "passive"))
      (node (ref "LED19") (pin "A") (pinfunction "A_A") (pintype "passive"))
      (node (ref "LED29") (pin "A") (pinfunction "A_A") (pintype "passive"))
      (node (ref "LED3") (pin "A") (pinfunction "A_A") (pintype "passive"))
      (node (ref "LED30") (pin "K") (pinfunction "C_K") (pintype "passive"))
      (node (ref "LED43") (pin "K") (pinfunction "C_K") (pintype "passive"))
      (node (ref "LED44") (pin "A") (pinfunction "A_A") (pintype "passive"))
      (node (ref "LED49") (pin "A") (pinfunction "A_A") (pintype "passive"))
      (node (ref "LED50") (pin "K") (pinfunction "C_K") (pintype "passive"))
      (node (ref "LED67") (pin "A") (pinfunction "A_A") (pintype "passive"))
      (node (ref "LED68") (pin "K") (pinfunction "C_K") (pintype "passive"))
      (node (ref "LED7") (pin "K") (pinfunction "C_K") (pintype "passive"))
      (node (ref "LED83") (pin "A") (pinfunction "A_A") (pintype "passive"))
      (node (ref "LED84") (pin "K") (pinfunction "C_K") (pintype "passive"))
      (node (ref "LED97") (pin "A") (pinfunction "A_A") (pintype "passive"))
      (node (ref "LED98") (pin "K") (pinfunction "C_K") (pintype "passive"))
      (node (ref "SV1") (pin "9") (pinfunction "9_9") (pintype "passive"))
    )
  )
)
